# pressure_stm_schematic.net
KiCad netlist of a schematic drawn in Altium Designer
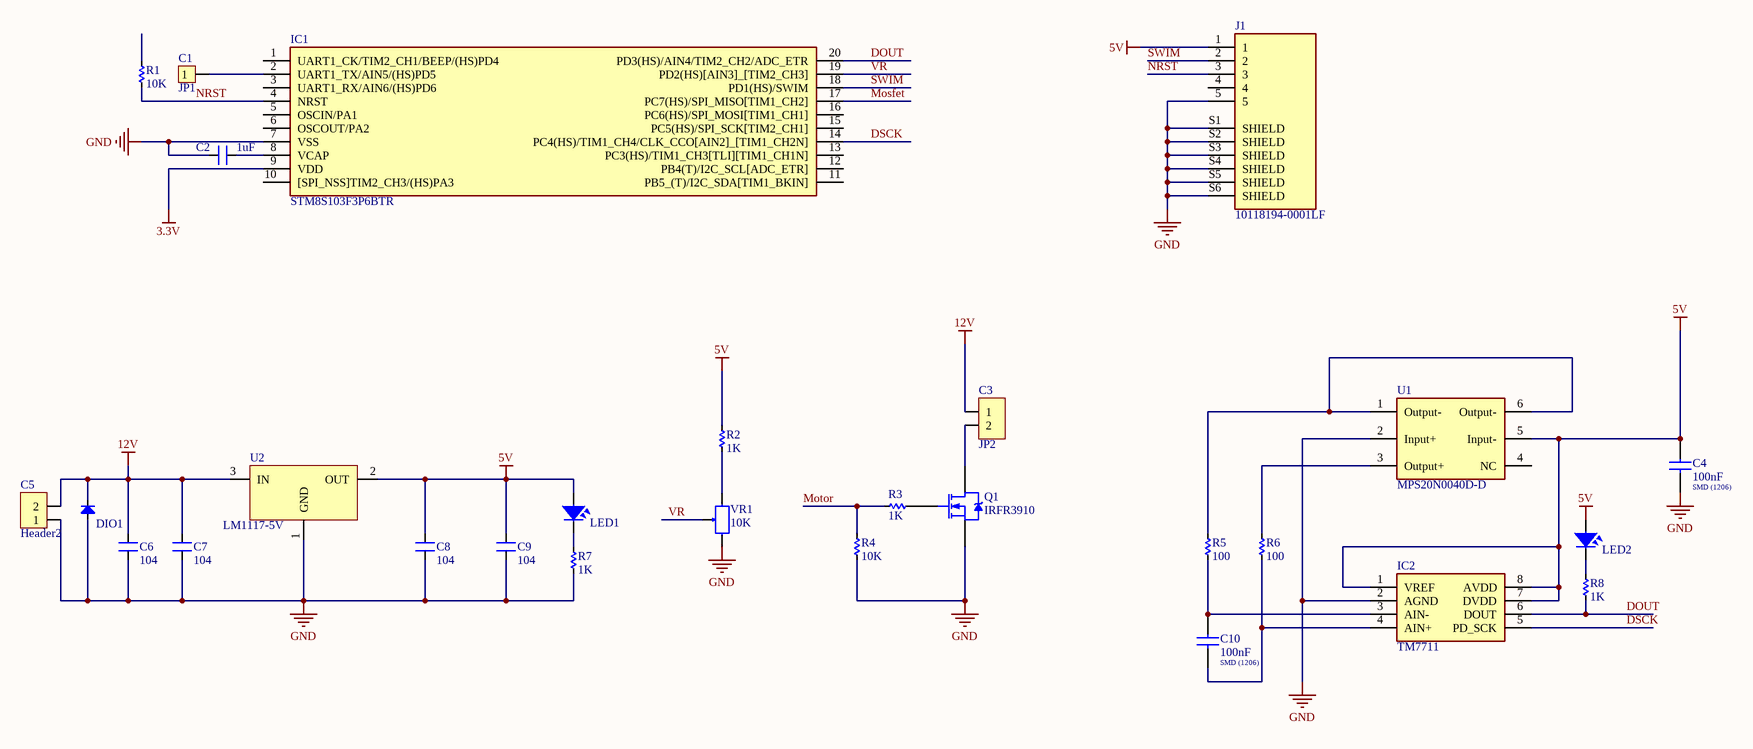
[diagram p0: pressure_stm_schematic.SchDoc]

(export (version "E")
  (design (tool "Eeschema 10.0.6"))
  (components
    (comp (ref "C1")
      (value "JP1")
      (footprint "JP1-D1T")
      (description "WR-PHD 2.54 mm Angled Socket Header")
      (fields
        (field (name "MANUFACTURER") "Würth Elektronik eiSos GmbH")
        (field (name "PARTNO") "613002143121")
        (field (name "CREATED BY") "Karrer Zheng")
      )
      (libsource (lib "LIBRARY") (part "JP1"))
    )
    (comp (ref "C2") (value "1uF") (footprint "CN-SMD-0805") (libsource (lib "LIBRARY") (part "CN")))
    (comp (ref "C3")
      (value "JP2")
      (footprint "JP2-D1T")
      (description "WR-PHD 2.54 mm Angled Socket Header")
      (fields
        (field (name "MANUFACTURER") "Würth Elektronik eiSos GmbH")
        (field (name "PARTNO") "613002143121")
        (field (name "CREATED BY") "Karrer Zheng")
      )
      (libsource (lib "LIBRARY") (part "JP2"))
    )
    (comp (ref "C4")
      (value "Capacitor SMD")
      (footprint "CAP_0603")
      (fields (field (name "VALOR") "100nF") (field (name "ENCAPSULAMENTO") "SMD (1206)"))
      (libsource (lib "Altium_Library_Brasil") (part "Capacitor SMD"))
    )
    (comp (ref "C5")
      (value "Header2")
      (footprint "Header2")
      (description "Header IDC, 2 x 1 Pin Vertical 2.54mm Pitch (Non-Boxed, Male)")
      (fields
        (field (name "MANUFACTURER") "Würth Elektronik eiSos GmbH")
        (field (name "PARTNO") "613002143121")
        (field (name "CREATED BY") "Karrer Zheng")
      )
      (libsource (lib "LIBRARY") (part "Header2"))
    )
    (comp (ref "C6")
      (value "104")
      (footprint "SM-CAP-0805")
      (fields (field (name "DESIGNED BY") "VanDungEvn"))
      (libsource (lib "electronicvn-library1") (part "CN"))
    )
    (comp (ref "C7")
      (value "104")
      (footprint "SM-CAP-0805")
      (fields (field (name "DESIGNED BY") "VanDungEvn"))
      (libsource (lib "electronicvn-library1") (part "CN"))
    )
    (comp (ref "C8")
      (value "104")
      (footprint "SM-CAP-0805")
      (fields (field (name "DESIGNED BY") "VanDungEvn"))
      (libsource (lib "electronicvn-library1") (part "CN"))
    )
    (comp (ref "C9")
      (value "104")
      (footprint "SM-CAP-0805")
      (fields (field (name "DESIGNED BY") "VanDungEvn"))
      (libsource (lib "electronicvn-library1") (part "CN"))
    )
    (comp (ref "C10")
      (value "Capacitor SMD")
      (footprint "CAP_0603")
      (fields (field (name "VALOR") "100nF") (field (name "ENCAPSULAMENTO") "SMD (1206)"))
      (libsource (lib "Altium_Library_Brasil") (part "Capacitor SMD"))
    )
    (comp (ref "DIO1")
      (value "Diode SMD")
      (footprint "DIO-SMD-106")
      (description "Default Diode")
      (fields (field (name "PUBLISHER") "Altium Limited"))
      (libsource (lib "LIBRARY") (part "Diode SMD"))
    )
    (comp (ref "IC1")
      (value "STM8S103F3P6BTR")
      (footprint "SamacSys:SOP65P640X120-20N")
      (description "Integrated Circuit")
      (libsource (lib "SamacSys") (part "STM8S103F3P6BTR"))
    )
    (comp (ref "IC2")
      (value "TM7711")
      (footprint "SamacSys:SOIC127P600X196-8N")
      (description "Integrated Circuit")
      (libsource (lib "*") (part "TM7711"))
    )
    (comp (ref "J1")
      (value "10118194-0001LF")
      (footprint "10118194-0001LF:AMPHENOL_10118194-0001LF")
      (description "USB - micro B USB 2.0 Receptacle Connector 5 Position Surface Mount, Right Angle; Through Hole")
      (fields (field (name "MF") "Amphenol ICC"))
      (libsource (lib "10118194-0001LF") (part "10118194-0001LF"))
    )
    (comp (ref "LED1") (value "LED") (footprint "LED-0805-Blue") (libsource (lib "LIBRARY") (part "LED SMD")))
    (comp (ref "LED2") (value "LED") (footprint "LED-0805-Blue") (libsource (lib "LIBRARY") (part "LED SMD")))
    (comp (ref "Q1")
      (value "IRFR3910")
      (footprint "TO-252AA_N")
      (description "HEXFET Power MOSFET")
      (fields (field (name "PUBLISHER") "Altium Limited"))
      (libsource (lib "IR Discrete MOSFET - Power") (part "IRFR3910"))
    )
    (comp (ref "R1")
      (value "10K")
      (footprint "RES-SMD-0805")
      (description "Resistor")
      (fields
        (field (name "MANUFACTURER") "Generic Components")
        (field (name "PUBLISHER") "Altium Hobart Technology Centre")
      )
      (libsource (lib "LIBRARY") (part "Res-SMD"))
    )
    (comp (ref "R2")
      (value "1K")
      (footprint "RES-SMD-0603")
      (description "Resistor")
      (fields
        (field (name "MANUFACTURER") "Generic Components")
        (field (name "PUBLISHER") "Altium Hobart Technology Centre")
      )
      (libsource (lib "LIBRARY") (part "Res-SMD"))
    )
    (comp (ref "R3")
      (value "1K")
      (footprint "RES-SMD-0603")
      (description "Resistor")
      (fields
        (field (name "MANUFACTURER") "Generic Components")
        (field (name "PUBLISHER") "Altium Hobart Technology Centre")
      )
      (libsource (lib "LIBRARY") (part "Res-SMD"))
    )
    (comp (ref "R4")
      (value "10K")
      (footprint "RES-SMD-0603")
      (description "Resistor")
      (fields
        (field (name "MANUFACTURER") "Generic Components")
        (field (name "PUBLISHER") "Altium Hobart Technology Centre")
      )
      (libsource (lib "LIBRARY") (part "Res-SMD"))
    )
    (comp (ref "R5")
      (value "100")
      (footprint "RES-SMD-0603")
      (description "Resistor")
      (fields
        (field (name "MANUFACTURER") "Generic Components")
        (field (name "PUBLISHER") "Altium Hobart Technology Centre")
      )
      (libsource (lib "LIBRARY") (part "Res-SMD"))
    )
    (comp (ref "R6")
      (value "100")
      (footprint "RES-SMD-0603")
      (description "Resistor")
      (fields
        (field (name "MANUFACTURER") "Generic Components")
        (field (name "PUBLISHER") "Altium Hobart Technology Centre")
      )
      (libsource (lib "LIBRARY") (part "Res-SMD"))
    )
    (comp (ref "R7")
      (value "1K")
      (footprint "RES-SMD-0603")
      (description "Resistor")
      (fields
        (field (name "MANUFACTURER") "Generic Components")
        (field (name "PUBLISHER") "Altium Hobart Technology Centre")
      )
      (libsource (lib "LIBRARY") (part "Res-SMD"))
    )
    (comp (ref "R8")
      (value "1K")
      (footprint "RES-SMD-0603")
      (description "Resistor")
      (fields
        (field (name "MANUFACTURER") "Generic Components")
        (field (name "PUBLISHER") "Altium Hobart Technology Centre")
      )
      (libsource (lib "LIBRARY") (part "Res-SMD"))
    )
    (comp (ref "U1")
      (value "MPS20N0040D-D")
      (footprint "MPS20N0040D-D:XDCR_ADP5241")
      (description "Pressure Sensor 14.5PSI (100kPa) Vented Gauge Male - 0.12 (3mm) Tube 0 V ~ 4.5 V 6-SMD Module")
      (fields (field (name "MP") "ADP5241") (field (name "MF") "Panasonic"))
      (libsource (lib "MPS20N0040D-D") (part "MPS20N0040D-D"))
    )
    (comp (ref "U2")
      (value "LM1117-5V")
      (footprint "SOT223")
      (description "800mA Low-Dropout Linear Regulator")
      (fields (field (name "CREATOR") "Nguyen Ba Bien"))
      (libsource (lib "LIBRARY") (part "LM1117"))
    )
    (comp (ref "VR1")
      (value "10K")
      (footprint "VR")
      (description "Var Resistor")
      (libsource (lib "LIBTanCN") (part "VR"))
    )
  )
  (nets
    (net (code "1") (name "/DOUT") (class "Default")
      (node (ref "IC1") (pin "20") (pinfunction "PD3(HS)/AIN4/TIM2_CH2/ADC_ETR_20") (pintype "passive"))
      (node (ref "IC2") (pin "6") (pinfunction "DOUT_6") (pintype "passive"))
      (node (ref "R8") (pin "2") (pinfunction "2_2") (pintype "passive"))
    )
    (net (code "2") (name "/DSCK") (class "Default")
      (node (ref "IC1") (pin "14") (pinfunction "PC4(HS)/TIM1_CH4/CLK_CCO[AIN2]_[TIM1_CH2N]_14") (pintype "passive"))
      (node (ref "IC2") (pin "5") (pinfunction "PD_SCK_5") (pintype "passive"))
    )
    (net (code "3") (name "/Mosfet") (class "Default")
      (node (ref "IC1") (pin "17") (pinfunction "PC7(HS)/SPI_MISO[TIM1_CH2]_17") (pintype "passive"))
    )
    (net (code "4") (name "/Motor") (class "Default")
      (node (ref "R3") (pin "1") (pinfunction "1_1") (pintype "passive"))
      (node (ref "R4") (pin "1") (pinfunction "1_1") (pintype "passive"))
    )
    (net (code "5") (name "/NRST") (class "Default")
      (node (ref "IC1") (pin "4") (pinfunction "NRST_4") (pintype "passive"))
      (node (ref "J1") (pin "3") (pinfunction "3_3") (pintype "passive"))
      (node (ref "R1") (pin "2") (pinfunction "2_2") (pintype "passive"))
    )
    (net (code "6") (name "/SWIM") (class "Default")
      (node (ref "IC1") (pin "18") (pinfunction "PD1(HS)/SWIM_18") (pintype "passive"))
      (node (ref "J1") (pin "2") (pinfunction "2_2") (pintype "passive"))
    )
    (net (code "7") (name "/VR") (class "Default")
      (node (ref "IC1") (pin "19") (pinfunction "PD2(HS)[AIN3]_[TIM2_CH3]_19") (pintype "passive"))
      (node (ref "VR1") (pin "2") (pinfunction "2_2") (pintype "passive"))
    )
    (net (code "8") (name "3.3V") (class "Default")
      (node (ref "IC1") (pin "9") (pinfunction "VDD_9") (pintype "passive"))
    )
    (net (code "9") (name "5V") (class "Default")
      (node (ref "C4") (pin "2") (pinfunction "2_2") (pintype "passive"))
      (node (ref "C8") (pin "2") (pinfunction "2_2") (pintype "passive"))
      (node (ref "C9") (pin "2") (pinfunction "2_2") (pintype "passive"))
      (node (ref "IC2") (pin "1") (pinfunction "VREF_1") (pintype "passive"))
      (node (ref "IC2") (pin "7") (pinfunction "DVDD_7") (pintype "passive"))
      (node (ref "IC2") (pin "8") (pinfunction "AVDD_8") (pintype "passive"))
      (node (ref "J1") (pin "1") (pinfunction "1_1") (pintype "passive"))
      (node (ref "LED1") (pin "1") (pinfunction "1_1") (pintype "passive"))
      (node (ref "LED2") (pin "1") (pinfunction "1_1") (pintype "passive"))
      (node (ref "R2") (pin "2") (pinfunction "2_2") (pintype "passive"))
      (node (ref "U1") (pin "5") (pinfunction "Input-_5") (pintype "power_in"))
      (node (ref "U2") (pin "2") (pinfunction "OUT_2") (pintype "passive"))
    )
    (net (code "10") (name "12V") (class "Default")
      (node (ref "C3") (pin "1") (pinfunction "1_1") (pintype "passive"))
      (node (ref "C5") (pin "2") (pinfunction "2_2") (pintype "passive"))
      (node (ref "C6") (pin "2") (pinfunction "2_2") (pintype "passive"))
      (node (ref "C7") (pin "2") (pinfunction "2_2") (pintype "passive"))
      (node (ref "DIO1") (pin "2") (pinfunction "K_2") (pintype "passive"))
      (node (ref "U2") (pin "3") (pinfunction "IN_3") (pintype "passive"))
    )
    (net (code "11") (name "GND") (class "Default")
      (node (ref "C2") (pin "2") (pinfunction "2_2") (pintype "passive"))
      (node (ref "C4") (pin "1") (pinfunction "1_1") (pintype "passive"))
      (node (ref "C5") (pin "1") (pinfunction "1_1") (pintype "passive"))
      (node (ref "C6") (pin "1") (pinfunction "1_1") (pintype "passive"))
      (node (ref "C7") (pin "1") (pinfunction "1_1") (pintype "passive"))
      (node (ref "C8") (pin "1") (pinfunction "1_1") (pintype "passive"))
      (node (ref "C9") (pin "1") (pinfunction "1_1") (pintype "passive"))
      (node (ref "DIO1") (pin "1") (pinfunction "A_1") (pintype "passive"))
      (node (ref "IC1") (pin "7") (pinfunction "VSS_7") (pintype "passive"))
      (node (ref "IC2") (pin "2") (pinfunction "AGND_2") (pintype "passive"))
      (node (ref "J1") (pin "5") (pinfunction "5_5") (pintype "passive"))
      (node (ref "J1") (pin "S1") (pinfunction "SHIELD_S1") (pintype "passive"))
      (node (ref "J1") (pin "S2") (pinfunction "SHIELD_S2") (pintype "passive"))
      (node (ref "J1") (pin "S3") (pinfunction "SHIELD_S3") (pintype "passive"))
      (node (ref "J1") (pin "S4") (pinfunction "SHIELD_S4") (pintype "passive"))
      (node (ref "J1") (pin "S5") (pinfunction "SHIELD_S5") (pintype "passive"))
      (node (ref "J1") (pin "S6") (pinfunction "SHIELD_S6") (pintype "passive"))
      (node (ref "Q1") (pin "3") (pinfunction "S_3") (pintype "passive"))
      (node (ref "R4") (pin "2") (pinfunction "2_2") (pintype "passive"))
      (node (ref "R7") (pin "2") (pinfunction "2_2") (pintype "passive"))
      (node (ref "U1") (pin "2") (pinfunction "Input+_2") (pintype "power_in"))
      (node (ref "U2") (pin "1") (pinfunction "GND_1") (pintype "passive"))
      (node (ref "VR1") (pin "1") (pinfunction "1_1") (pintype "passive"))
    )
    (net (code "12") (name "Net-(IC1-UART1_TX{slash}AIN5{slash}(HS)PD5)") (class "Default")
      (node (ref "C1") (pin "1") (pinfunction "1_1") (pintype "passive"))
      (node (ref "IC1") (pin "2") (pinfunction "UART1_TX/AIN5/(HS)PD5_2") (pintype "passive"))
    )
    (net (code "13") (name "Net-(IC1-VCAP)") (class "Default")
      (node (ref "C2") (pin "1") (pinfunction "1_1") (pintype "passive"))
      (node (ref "IC1") (pin "8") (pinfunction "VCAP_8") (pintype "passive"))
    )
    (net (code "14") (name "Net-(IC2-AIN+)") (class "Default")
      (node (ref "C10") (pin "1") (pinfunction "1_1") (pintype "passive"))
      (node (ref "IC2") (pin "4") (pinfunction "AIN+_4") (pintype "passive"))
      (node (ref "R6") (pin "2") (pinfunction "2_2") (pintype "passive"))
    )
    (net (code "15") (name "Net-(IC2-AIN-)") (class "Default")
      (node (ref "C10") (pin "2") (pinfunction "2_2") (pintype "passive"))
      (node (ref "IC2") (pin "3") (pinfunction "AIN-_3") (pintype "passive"))
      (node (ref "R5") (pin "2") (pinfunction "2_2") (pintype "passive"))
    )
    (net (code "16") (name "Net-(LED1-Pad2)") (class "Default")
      (node (ref "LED1") (pin "2") (pinfunction "2_2") (pintype "passive"))
      (node (ref "R7") (pin "1") (pinfunction "1_1") (pintype "passive"))
    )
    (net (code "17") (name "Net-(LED2-Pad2)") (class "Default")
      (node (ref "LED2") (pin "2") (pinfunction "2_2") (pintype "passive"))
      (node (ref "R8") (pin "1") (pinfunction "1_1") (pintype "passive"))
    )
    (net (code "18") (name "Net-(Q1-D)") (class "Default")
      (node (ref "C3") (pin "2") (pinfunction "2_2") (pintype "passive"))
      (node (ref "Q1") (pin "4") (pinfunction "D_4") (pintype "passive"))
    )
    (net (code "19") (name "Net-(Q1-G)") (class "Default")
      (node (ref "Q1") (pin "1") (pinfunction "G_1") (pintype "passive"))
      (node (ref "R3") (pin "2") (pinfunction "2_2") (pintype "passive"))
    )
    (net (code "20") (name "Net-(R2-Pad1)") (class "Default")
      (node (ref "R2") (pin "1") (pinfunction "1_1") (pintype "passive"))
      (node (ref "VR1") (pin "3") (pinfunction "3_3") (pintype "passive"))
    )
    (net (code "21") (name "Net-(R5-Pad1)") (class "Default")
      (node (ref "R5") (pin "1") (pinfunction "1_1") (pintype "passive"))
      (node (ref "U1") (pin "1") (pinfunction "Output-_1") (pintype "power_in"))
      (node (ref "U1") (pin "6") (pinfunction "Output-_6") (pintype "power_in"))
    )
    (net (code "22") (name "Net-(U1-Output+)") (class "Default")
      (node (ref "R6") (pin "1") (pinfunction "1_1") (pintype "passive"))
      (node (ref "U1") (pin "3") (pinfunction "Output+_3") (pintype "power_in"))
    )
    (net (code "23") (name "unconnected-(IC1-OSCIN{slash}PA1-Pad5)") (class "Default")
      (node (ref "IC1") (pin "5") (pinfunction "OSCIN/PA1_5") (pintype "passive"))
    )
    (net (code "24") (name "unconnected-(IC1-OSCOUT{slash}PA2-Pad6)") (class "Default")
      (node (ref "IC1") (pin "6") (pinfunction "OSCOUT/PA2_6") (pintype "passive"))
    )
    (net (code "25") (name "unconnected-(IC1-PB4(T){slash}I2C_SCL[ADC_ETR]-Pad12)") (class "Default")
      (node (ref "IC1") (pin "12") (pinfunction "PB4(T)/I2C_SCL[ADC_ETR]_12") (pintype "passive"))
    )
    (net (code "26") (name "unconnected-(IC1-PB5_(T){slash}I2C_SDA[TIM1_BKIN]-Pad11)") (class "Default")
      (node (ref "IC1") (pin "11") (pinfunction "PB5_(T)/I2C_SDA[TIM1_BKIN]_11") (pintype "passive"))
    )
    (net (code "27") (name "unconnected-(IC1-PC3(HS){slash}TIM1_CH3[TLI][TIM1_CH1N]-Pad13)") (class "Default")
      (node (ref "IC1") (pin "13") (pinfunction "PC3(HS)/TIM1_CH3[TLI][TIM1_CH1N]_13") (pintype "passive"))
    )
    (net (code "28") (name "unconnected-(IC1-PC5(HS){slash}SPI_SCK[TIM2_CH1]-Pad15)") (class "Default")
      (node (ref "IC1") (pin "15") (pinfunction "PC5(HS)/SPI_SCK[TIM2_CH1]_15") (pintype "passive"))
    )
    (net (code "29") (name "unconnected-(IC1-PC6(HS){slash}SPI_MOSI[TIM1_CH1]-Pad16)") (class "Default")
      (node (ref "IC1") (pin "16") (pinfunction "PC6(HS)/SPI_MOSI[TIM1_CH1]_16") (pintype "passive"))
    )
    (net (code "30") (name "unconnected-(IC1-UART1_CK{slash}TIM2_CH1{slash}BEEP{slash}(HS)PD4-Pad1)") (class "Default")
      (node (ref "IC1") (pin "1") (pinfunction "UART1_CK/TIM2_CH1/BEEP/(HS)PD4_1") (pintype "passive"))
    )
    (net (code "31") (name "unconnected-(IC1-UART1_RX{slash}AIN6{slash}(HS)PD6-Pad3)") (class "Default")
      (node (ref "IC1") (pin "3") (pinfunction "UART1_RX/AIN6/(HS)PD6_3") (pintype "passive"))
    )
    (net (code "32") (name "unconnected-(IC1-[SPI_NSS]TIM2_CH3{slash}(HS)PA3-Pad10)") (class "Default")
      (node (ref "IC1") (pin "10") (pinfunction "[SPI_NSS]TIM2_CH3/(HS)PA3_10") (pintype "passive"))
    )
    (net (code "33") (name "unconnected-(J1-Pad4)") (class "Default")
      (node (ref "J1") (pin "4") (pinfunction "4_4") (pintype "passive"))
    )
    (net (code "34") (name "unconnected-(R1-Pad1)") (class "Default")
      (node (ref "R1") (pin "1") (pinfunction "1_1") (pintype "passive"))
    )
    (net (code "35") (name "unconnected-(U1-NC-Pad4)") (class "Default")
      (node (ref "U1") (pin "4") (pinfunction "NC_4") (pintype "power_in"))
    )
  )
)
